# dasblinkenhat-controller-mk-1_0.net
KiCad netlist of a schematic drawn in EAGLE
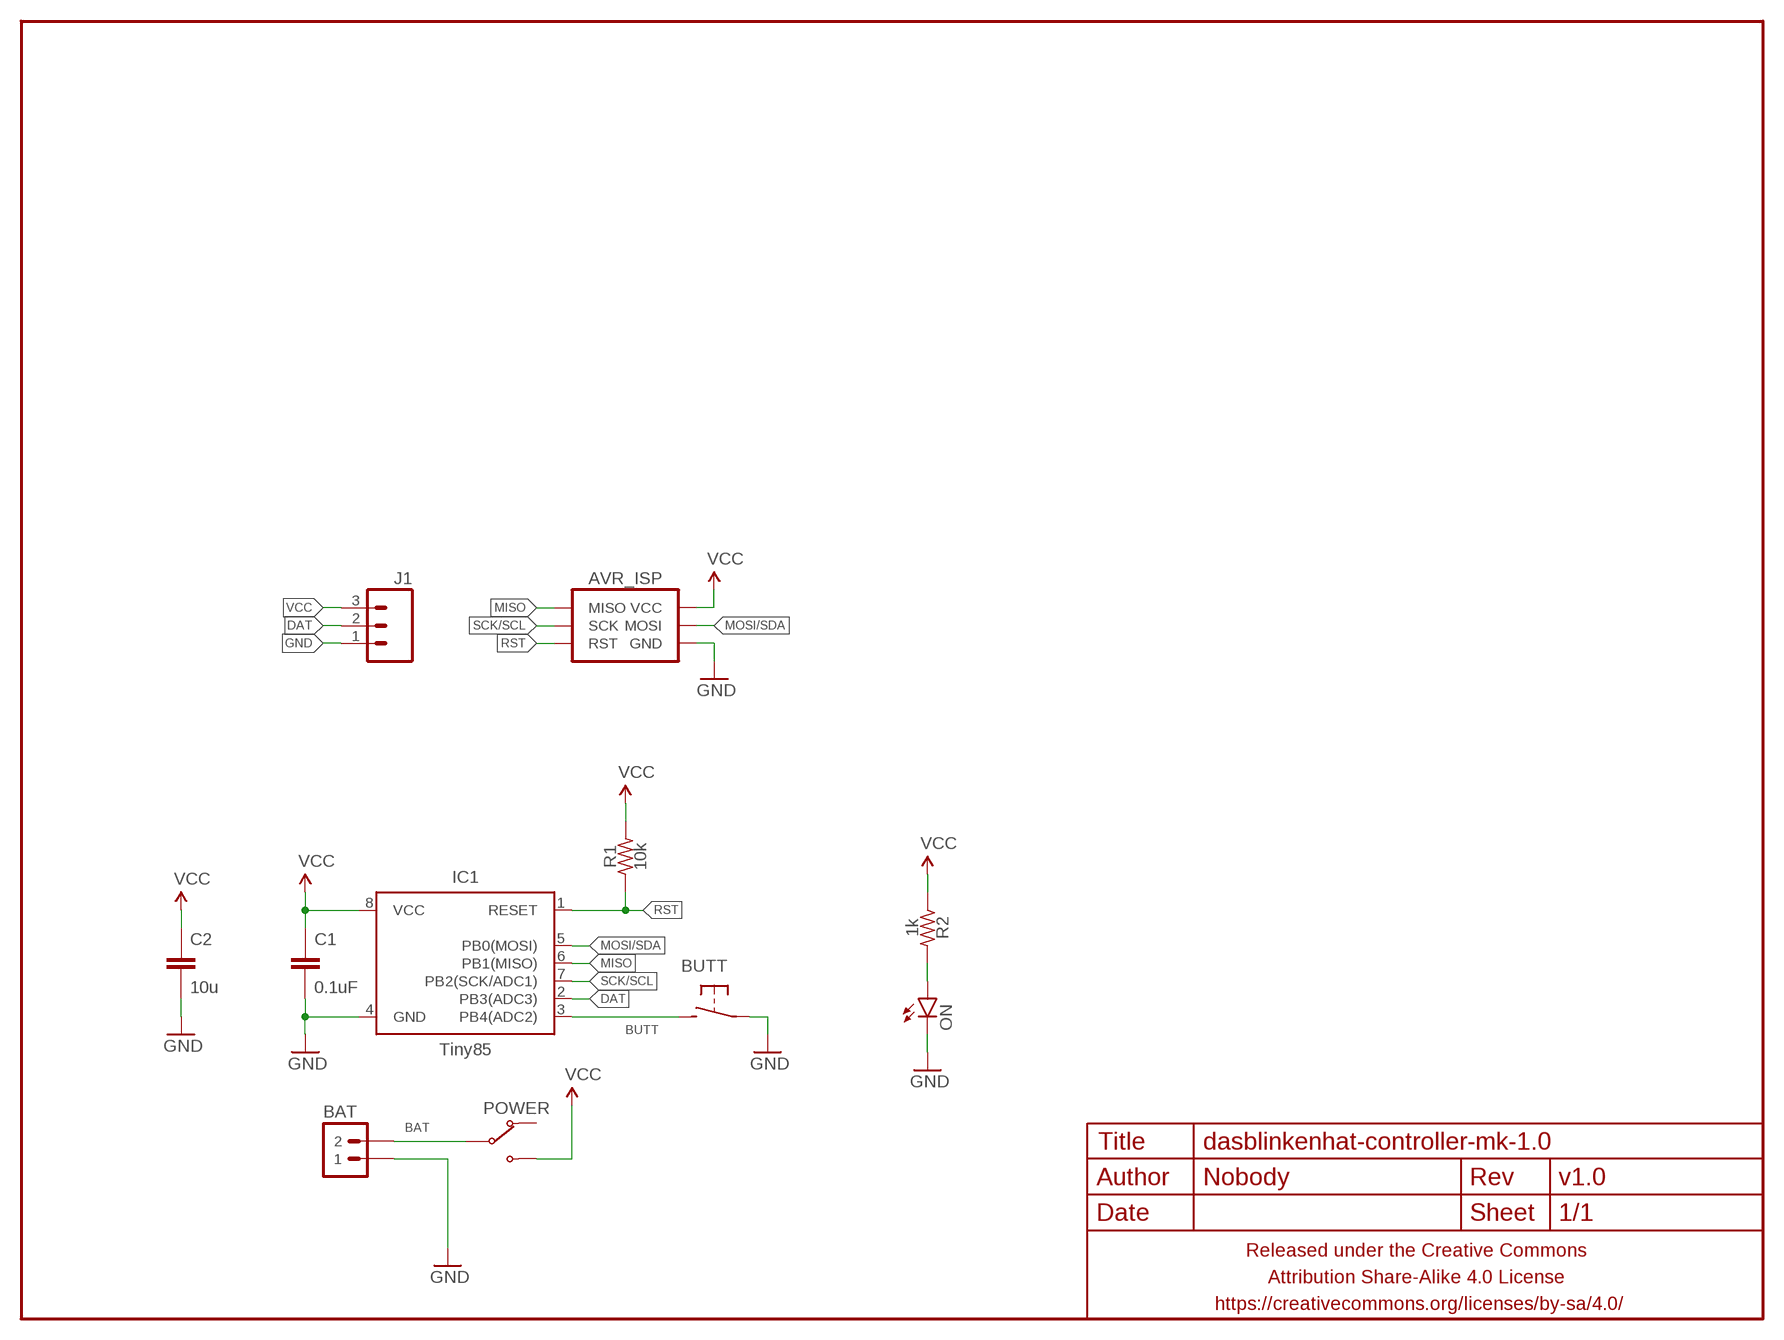
[diagram p0: schematic, sheet 1]

(export (version "E")
  (design (tool "Eeschema 10.0.6"))
  (components
    (comp (ref "AVR_ISP")
      (value "AVR_SPI_PRG_6TESTPOINTS")
      (footprint "eagle-import:2X3_TEST_POINTS")
      (libsource (lib "eagle-import") (part "AVR_SPI_PRG_6TESTPOINTS"))
    )
    (comp (ref "BAT")
      (value "M02JST-PTH-RA-R+")
      (footprint "eagle-import:JST-2-PH-RA-PTH-R+")
      (libsource (lib "eagle-import") (part "M02JST-PTH-RA-R+"))
    )
    (comp (ref "BUTT")
      (value "DTS-6MM")
      (footprint "eagle-import:DTSM-6")
      (libsource (lib "eagle-import") (part "SPST-NO-TACT6MM-SMD"))
    )
    (comp (ref "C1")
      (value "0.1uF")
      (footprint "eagle-import:C0603")
      (libsource (lib "eagle-import") (part "CAPACITOR-CERAMICC0603"))
    )
    (comp (ref "C2")
      (value "10u")
      (footprint "eagle-import:C0805")
      (libsource (lib "eagle-import") (part "CAPACITOR-CERAMICC0805"))
    )
    (comp (ref "FRAME1")
      (value "FRAME-LETTERNO_PACKAGE")
      (footprint "eagle-import:DUMMY")
      (fields (field (name "VERSION") "v1.0") (field (name "DESIGNER") "Nobody"))
      (libsource (lib "eagle-import") (part "FRAME-LETTERNO_PACKAGE"))
    )
    (comp (ref "IC1")
      (value "Tiny85")
      (footprint "eagle-import:SO08-EIAJ")
      (libsource (lib "eagle-import") (part "ATTINY45TINY85-20-SOICW"))
    )
    (comp (ref "J1")
      (value "M03JST-XH-RA-PTH")
      (footprint "eagle-import:JST-3-XH-RA-PTH")
      (libsource (lib "eagle-import") (part "M03JST-XH-RA-PTH"))
    )
    (comp (ref "ON")
      (value "LED0603")
      (footprint "eagle-import:LED-0603")
      (libsource (lib "eagle-import") (part "LED0603"))
    )
    (comp (ref "POWER")
      (value "SWITCH-SPDTSMD-RA")
      (footprint "eagle-import:SWITCH-SPDT-SMD-RA")
      (libsource (lib "eagle-import") (part "SWITCH-SPDTSMD-RA"))
    )
    (comp (ref "R1")
      (value "10k")
      (footprint "eagle-import:R0603")
      (libsource (lib "eagle-import") (part "RESISTORR0603"))
    )
    (comp (ref "R2")
      (value "1k")
      (footprint "eagle-import:R0603")
      (libsource (lib "eagle-import") (part "RESISTORR0603"))
    )
  )
  (nets
    (net (code "1") (name "/BAT") (class "Default")
      (node (ref "BAT") (pin "2") (pinfunction "2_2") (pintype "passive"))
      (node (ref "POWER") (pin "2") (pinfunction "COM_2") (pintype "passive"))
    )
    (net (code "2") (name "/BUTT") (class "Default")
      (node (ref "BUTT") (pin "3") (pinfunction "2_3") (pintype "passive"))
      (node (ref "BUTT") (pin "4") (pinfunction "2_4") (pintype "passive"))
      (node (ref "IC1") (pin "3") (pinfunction "PB4(ADC2)_3") (pintype "bidirectional"))
    )
    (net (code "3") (name "DAT") (class "Default")
      (node (ref "IC1") (pin "2") (pinfunction "PB3(ADC3)_2") (pintype "bidirectional"))
      (node (ref "J1") (pin "2") (pinfunction "2_2") (pintype "passive"))
    )
    (net (code "4") (name "GND") (class "Default")
      (node (ref "AVR_ISP") (pin "6") (pinfunction "GND_6") (pintype "passive"))
      (node (ref "BAT") (pin "1") (pinfunction "1_1") (pintype "passive"))
      (node (ref "BUTT") (pin "1") (pinfunction "1_1") (pintype "passive"))
      (node (ref "BUTT") (pin "2") (pinfunction "1_2") (pintype "passive"))
      (node (ref "C1") (pin "2") (pinfunction "2_2") (pintype "passive"))
      (node (ref "C2") (pin "2") (pinfunction "2_2") (pintype "passive"))
      (node (ref "IC1") (pin "4") (pinfunction "GND_4") (pintype "bidirectional"))
      (node (ref "J1") (pin "1") (pinfunction "1_1") (pintype "passive"))
      (node (ref "ON") (pin "C") (pinfunction "C_C") (pintype "passive"))
    )
    (net (code "5") (name "MISO") (class "Default")
      (node (ref "AVR_ISP") (pin "1") (pinfunction "MISO_1") (pintype "passive"))
      (node (ref "IC1") (pin "6") (pinfunction "PB1(MISO)_6") (pintype "bidirectional"))
    )
    (net (code "6") (name "MOSI{slash}SDA") (class "Default")
      (node (ref "AVR_ISP") (pin "4") (pinfunction "MOSI_4") (pintype "passive"))
      (node (ref "IC1") (pin "5") (pinfunction "PB0(MOSI)_5") (pintype "bidirectional"))
    )
    (net (code "7") (name "Net-(ON-PadA)") (class "Default")
      (node (ref "ON") (pin "A") (pinfunction "A_A") (pintype "passive"))
      (node (ref "R2") (pin "2") (pinfunction "2_2") (pintype "passive"))
    )
    (net (code "8") (name "RST") (class "Default")
      (node (ref "AVR_ISP") (pin "5") (pinfunction "RST_5") (pintype "passive"))
      (node (ref "IC1") (pin "1") (pinfunction "RESET_1") (pintype "bidirectional"))
      (node (ref "R1") (pin "1") (pinfunction "1_1") (pintype "passive"))
    )
    (net (code "9") (name "SCK{slash}SCL") (class "Default")
      (node (ref "AVR_ISP") (pin "3") (pinfunction "SCK_3") (pintype "passive"))
      (node (ref "IC1") (pin "7") (pinfunction "PB2(SCK/ADC1)_7") (pintype "bidirectional"))
    )
    (net (code "10") (name "VCC") (class "Default")
      (node (ref "AVR_ISP") (pin "2") (pinfunction "VCC_2") (pintype "passive"))
      (node (ref "C1") (pin "1") (pinfunction "1_1") (pintype "passive"))
      (node (ref "C2") (pin "1") (pinfunction "1_1") (pintype "passive"))
      (node (ref "IC1") (pin "8") (pinfunction "VCC_8") (pintype "bidirectional"))
      (node (ref "J1") (pin "3") (pinfunction "3_3") (pintype "passive"))
      (node (ref "POWER") (pin "1") (pinfunction "NO_1") (pintype "passive"))
      (node (ref "R1") (pin "2") (pinfunction "2_2") (pintype "passive"))
      (node (ref "R2") (pin "1") (pinfunction "1_1") (pintype "passive"))
    )
    (net (code "11") (name "unconnected-(POWER-NC-Pad3)") (class "Default")
      (node (ref "POWER") (pin "3") (pinfunction "NC_3") (pintype "passive"))
    )
  )
)
